# 4-RF-PD.net
KiCad netlist of a schematic drawn in Altium Designer
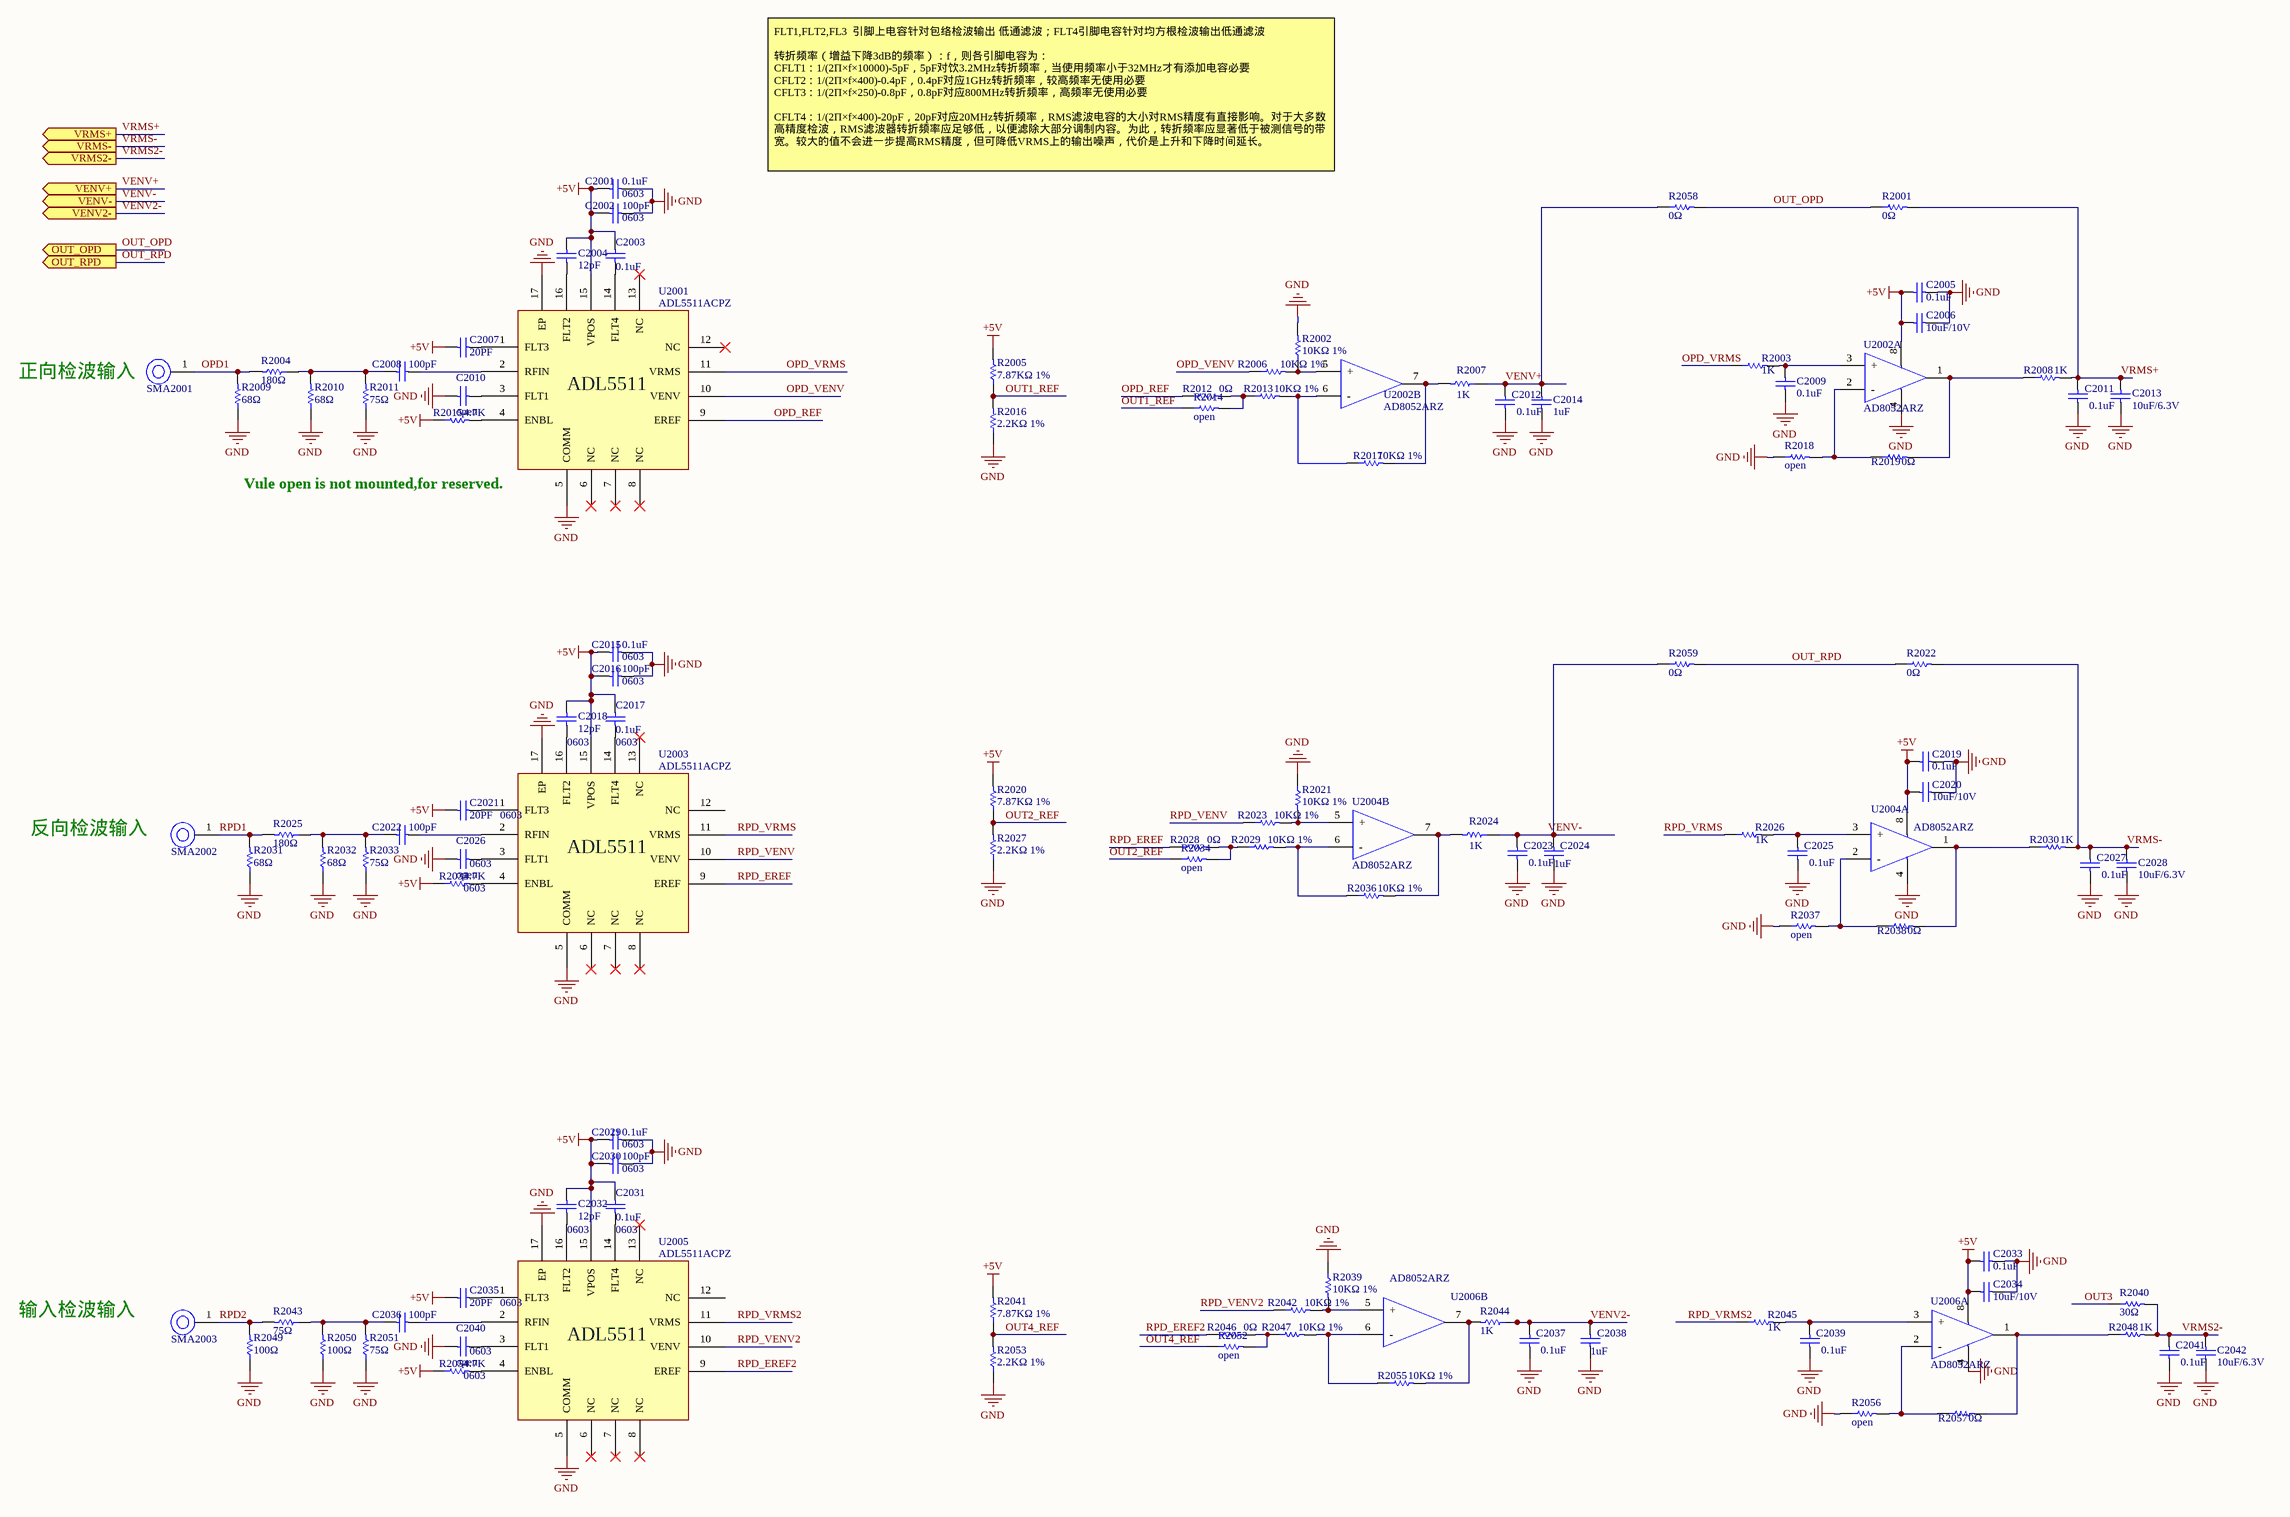
[diagram p0: 4-RF-PD.SchDoc]

(export (version "E")
  (design (tool "Eeschema 10.0.6"))
  (components
    (comp (ref "C2001")
      (value "0.1uF")
      (footprint "C0603")
      (description "贴片电容_GRM188R71H104KA01D_0.1uF±10%,50V,0603")
      (libsource (lib "20贴片电容0603") (part "0.1uF贴片电容"))
    )
    (comp (ref "C2002")
      (value "100pF")
      (footprint "C0603")
      (description "贴片电容_100pF±10%,50V,0603")
      (libsource (lib "20贴片电容0603") (part "1000pF贴片电容"))
    )
    (comp (ref "C2003")
      (value "0.1uF")
      (footprint "C0603")
      (description "贴片电容_GRM188R71H104KA01D_0.1uF±10%,50V,0603")
      (libsource (lib "20贴片电容0603") (part "0.1uF贴片电容"))
    )
    (comp (ref "C2004")
      (value "12pF")
      (footprint "C0603")
      (description "GRM1885C1H390JA01D_39pF±5%,50V,0603")
      (libsource (lib "20贴片电容0603") (part "10pF贴片电容"))
    )
    (comp (ref "C2005")
      (value "0.1uF")
      (footprint "C0603")
      (description "贴片电容_GRM188R71H104KA01D_0.1uF±10%,50V,0603")
      (libsource (lib "20贴片电容0603") (part "0.1uF贴片电容"))
    )
    (comp (ref "C2006")
      (value "10uF/10V")
      (footprint "C0805")
      (description "贴片电容_GRM21BR61A106KE19L_10uF±10%,10V,0805")
      (libsource (lib "21贴片电容0805") (part "10uF贴片电容"))
    )
    (comp (ref "C2007")
      (value "20PF")
      (footprint "C0603")
      (description "贴片电容_GRM1885C1H680JA01D_0603,68PF,50V,±5％,COG")
      (fields (field (name "MPN") "Murata"))
      (libsource (lib "20贴片电容0603") (part "10pF贴片电容"))
    )
    (comp (ref "C2008")
      (value "100pF")
      (footprint "C0805")
      (description "贴片电容_GRM2165C1H101JA01D_100pF±5%,50V,0805")
      (libsource (lib "21贴片电容0805") (part "100pF贴片电容"))
    )
    (comp (ref "C2009")
      (value "0.1uF")
      (footprint "C0603")
      (description "贴片电容_GRM188R71H104KA01D_0.1uF±10%,50V,0603")
      (libsource (lib "20贴片电容0603") (part "0.1uF贴片电容"))
    )
    (comp (ref "C2010")
      (value "open")
      (footprint "C0603")
      (description "贴片电容_GRM188R71H102KA01_1000pF±10%,50V,0603")
      (libsource (lib "20贴片电容0603") (part "1000pF贴片电容"))
    )
    (comp (ref "C2011")
      (value "0.1uF")
      (footprint "C0603")
      (description "贴片电容_GRM188R71H104KA01D_0.1uF±10%,50V,0603")
      (libsource (lib "20贴片电容0603") (part "0.1uF贴片电容"))
    )
    (comp (ref "C2012")
      (value "0.1uF")
      (footprint "C0603")
      (description "贴片电容_GRM188R71H104KA01D_0.1uF±10%,50V,0603")
      (libsource (lib "20贴片电容0603") (part "0.1uF贴片电容"))
    )
    (comp (ref "C2013")
      (value "10uF/6.3V")
      (footprint "C0603")
      (description "贴片电容_GRM188R60J106ME47D_10uF±20%,6.3V,0603")
      (libsource (lib "20贴片电容0603") (part "10uF贴片电容"))
    )
    (comp (ref "C2014") (value "1uF") (footprint "C0603") (libsource (lib "20贴片电容0603") (part "10uF贴片电容")))
    (comp (ref "C2015")
      (value "0.1uF")
      (footprint "C0603")
      (description "贴片电容_GRM188R71H104KA01D_0.1uF±10%,50V,0603")
      (libsource (lib "20贴片电容0603") (part "0.1uF贴片电容"))
    )
    (comp (ref "C2016")
      (value "100pF")
      (footprint "C0603")
      (description "贴片电容_100pF±10%,50V,0603")
      (libsource (lib "20贴片电容0603") (part "1000pF贴片电容"))
    )
    (comp (ref "C2017")
      (value "0.1uF")
      (footprint "C0603")
      (description "贴片电容_GRM188R71H104KA01D_0.1uF±10%,50V,0603")
      (libsource (lib "20贴片电容0603") (part "0.1uF贴片电容"))
    )
    (comp (ref "C2018")
      (value "12pF")
      (footprint "C0603")
      (description "GRM1885C1H390JA01D_39pF±5%,50V,0603")
      (libsource (lib "20贴片电容0603") (part "10pF贴片电容"))
    )
    (comp (ref "C2019")
      (value "0.1uF")
      (footprint "C0603")
      (description "贴片电容_GRM188R71H104KA01D_0.1uF±10%,50V,0603")
      (libsource (lib "20贴片电容0603") (part "0.1uF贴片电容"))
    )
    (comp (ref "C2020")
      (value "10uF/10V")
      (footprint "C0805")
      (description "贴片电容_GRM21BR61A106KE19L_10uF±10%,10V,0805")
      (libsource (lib "21贴片电容0805") (part "10uF贴片电容"))
    )
    (comp (ref "C2021")
      (value "20PF")
      (footprint "C0603")
      (description "贴片电容_GRM1885C1H680JA01D_0603,68PF,50V,±5％,COG")
      (fields (field (name "MPN") "Murata"))
      (libsource (lib "20贴片电容0603") (part "10pF贴片电容"))
    )
    (comp (ref "C2022")
      (value "100pF")
      (footprint "C0805")
      (description "贴片电容_GRM2165C1H101JA01D_100pF±5%,50V,0805")
      (libsource (lib "21贴片电容0805") (part "100pF贴片电容"))
    )
    (comp (ref "C2023")
      (value "0.1uF")
      (footprint "C0603")
      (description "贴片电容_GRM188R71H104KA01D_0.1uF±10%,50V,0603")
      (libsource (lib "20贴片电容0603") (part "0.1uF贴片电容"))
    )
    (comp (ref "C2024") (value "1uF") (footprint "C0603") (libsource (lib "20贴片电容0603") (part "10uF贴片电容")))
    (comp (ref "C2025")
      (value "0.1uF")
      (footprint "C0603")
      (description "贴片电容_GRM188R71H104KA01D_0.1uF±10%,50V,0603")
      (libsource (lib "20贴片电容0603") (part "0.1uF贴片电容"))
    )
    (comp (ref "C2026")
      (value "open")
      (footprint "C0603")
      (description "贴片电容_GRM188R71H102KA01_1000pF±10%,50V,0603")
      (libsource (lib "20贴片电容0603") (part "1000pF贴片电容"))
    )
    (comp (ref "C2027")
      (value "0.1uF")
      (footprint "C0603")
      (description "贴片电容_GRM188R71H104KA01D_0.1uF±10%,50V,0603")
      (libsource (lib "20贴片电容0603") (part "0.1uF贴片电容"))
    )
    (comp (ref "C2028")
      (value "10uF/6.3V")
      (footprint "C0603")
      (description "贴片电容_GRM188R60J106ME47D_10uF±20%,6.3V,0603")
      (libsource (lib "20贴片电容0603") (part "10uF贴片电容"))
    )
    (comp (ref "C2029")
      (value "0.1uF")
      (footprint "C0603")
      (description "贴片电容_GRM188R71H104KA01D_0.1uF±10%,50V,0603")
      (libsource (lib "20贴片电容0603") (part "0.1uF贴片电容"))
    )
    (comp (ref "C2030")
      (value "100pF")
      (footprint "C0603")
      (description "贴片电容_100pF±10%,50V,0603")
      (libsource (lib "20贴片电容0603") (part "1000pF贴片电容"))
    )
    (comp (ref "C2031")
      (value "0.1uF")
      (footprint "C0603")
      (description "贴片电容_GRM188R71H104KA01D_0.1uF±10%,50V,0603")
      (libsource (lib "20贴片电容0603") (part "0.1uF贴片电容"))
    )
    (comp (ref "C2032")
      (value "12pF")
      (footprint "C0603")
      (description "GRM1885C1H390JA01D_39pF±5%,50V,0603")
      (libsource (lib "20贴片电容0603") (part "10pF贴片电容"))
    )
    (comp (ref "C2033")
      (value "0.1uF")
      (footprint "C0603")
      (description "贴片电容_GRM188R71H104KA01D_0.1uF±10%,50V,0603")
      (libsource (lib "20贴片电容0603") (part "0.1uF贴片电容"))
    )
    (comp (ref "C2034")
      (value "10uF/10V")
      (footprint "C0805")
      (description "贴片电容_GRM21BR61A106KE19L_10uF±10%,10V,0805")
      (libsource (lib "21贴片电容0805") (part "10uF贴片电容"))
    )
    (comp (ref "C2035")
      (value "20PF")
      (footprint "C0603")
      (description "贴片电容_GRM1885C1H680JA01D_0603,68PF,50V,±5％,COG")
      (fields (field (name "MPN") "Murata"))
      (libsource (lib "20贴片电容0603") (part "10pF贴片电容"))
    )
    (comp (ref "C2036")
      (value "100pF")
      (footprint "C0805")
      (description "贴片电容_GRM2165C1H101JA01D_100pF±5%,50V,0805")
      (libsource (lib "21贴片电容0805") (part "100pF贴片电容"))
    )
    (comp (ref "C2037")
      (value "0.1uF")
      (footprint "C0603")
      (description "贴片电容_GRM188R71H104KA01D_0.1uF±10%,50V,0603")
      (libsource (lib "20贴片电容0603") (part "0.1uF贴片电容"))
    )
    (comp (ref "C2038") (value "1uF") (footprint "C0603") (libsource (lib "20贴片电容0603") (part "10uF贴片电容")))
    (comp (ref "C2039")
      (value "0.1uF")
      (footprint "C0603")
      (description "贴片电容_GRM188R71H104KA01D_0.1uF±10%,50V,0603")
      (libsource (lib "20贴片电容0603") (part "0.1uF贴片电容"))
    )
    (comp (ref "C2040")
      (value "open")
      (footprint "C0603")
      (description "贴片电容_GRM188R71H102KA01_1000pF±10%,50V,0603")
      (libsource (lib "20贴片电容0603") (part "1000pF贴片电容"))
    )
    (comp (ref "C2041")
      (value "0.1uF")
      (footprint "C0603")
      (description "贴片电容_GRM188R71H104KA01D_0.1uF±10%,50V,0603")
      (libsource (lib "20贴片电容0603") (part "0.1uF贴片电容"))
    )
    (comp (ref "C2042")
      (value "10uF/6.3V")
      (footprint "C0603")
      (description "贴片电容_GRM188R60J106ME47D_10uF±20%,6.3V,0603")
      (libsource (lib "20贴片电容0603") (part "10uF贴片电容"))
    )
    (comp (ref "R2001") (value "0Ω") (footprint "R0603") (libsource (lib "10贴片电阻0603") (part "0Ω贴片电阻")))
    (comp (ref "R2002")
      (value "10KΩ 1%")
      (footprint "R0603")
      (libsource (lib "10贴片电阻0603") (part "430Ω贴片电阻"))
    )
    (comp (ref "R2003")
      (value "1K")
      (footprint "R0603")
      (description "贴片电阻_1K±5%,0603")
      (libsource (lib "10贴片电阻0603") (part "1K贴片电阻"))
    )
    (comp (ref "R2004")
      (value "180Ω")
      (footprint "R1206")
      (description "贴片电阻_1206,180Ω,±5％")
      (libsource (lib "12贴片电阻1206") (part "56Ω贴片电阻"))
    )
    (comp (ref "R2005")
      (value "7.87KΩ 1%")
      (footprint "R0603")
      (description "0603,7.87KΩ,±1％")
      (libsource (lib "10贴片电阻0603") (part "0Ω贴片电阻"))
    )
    (comp (ref "R2006")
      (value "10KΩ 1%")
      (footprint "R0603")
      (libsource (lib "10贴片电阻0603") (part "430Ω贴片电阻"))
    )
    (comp (ref "R2007") (value "1K") (footprint "R0603") (libsource (lib "10贴片电阻0603") (part "0Ω贴片电阻")))
    (comp (ref "R2008")
      (value "1K")
      (footprint "R0603")
      (description "贴片电阻_0Ω±5%,0603")
      (libsource (lib "10贴片电阻0603") (part "0Ω贴片电阻"))
    )
    (comp (ref "R2009")
      (value "68Ω")
      (footprint "R1206")
      (description "贴片电阻_68Ω±5%,1206")
      (libsource (lib "12贴片电阻1206") (part "56Ω贴片电阻"))
    )
    (comp (ref "R2010")
      (value "68Ω")
      (footprint "R1206")
      (description "贴片电阻_68Ω±5%,1206")
      (libsource (lib "12贴片电阻1206") (part "56Ω贴片电阻"))
    )
    (comp (ref "R2011")
      (value "75Ω")
      (footprint "R0805")
      (description "贴片电阻_75Ω±5%,0805")
      (libsource (lib "11贴片电阻0805") (part "75Ω贴片电阻"))
    )
    (comp (ref "R2012")
      (value "0Ω")
      (footprint "R0603")
      (description "贴片电阻_0Ω±5%,0603")
      (libsource (lib "10贴片电阻0603") (part "0Ω贴片电阻"))
    )
    (comp (ref "R2013")
      (value "10KΩ 1%")
      (footprint "R0603")
      (libsource (lib "10贴片电阻0603") (part "430Ω贴片电阻"))
    )
    (comp (ref "R2014")
      (value "open")
      (footprint "R0603")
      (description "贴片电阻_0Ω±5%,0603")
      (libsource (lib "10贴片电阻0603") (part "0Ω贴片电阻"))
    )
    (comp (ref "R2015")
      (value "4.7K")
      (footprint "R0603")
      (description "贴片电阻_4.7K±5%,0603")
      (libsource (lib "10贴片电阻0603") (part "4.7K贴片电阻"))
    )
    (comp (ref "R2016")
      (value "2.2KΩ 1%")
      (footprint "R0603")
      (description "0603,2.2KΩ,±1％")
      (libsource (lib "10贴片电阻0603") (part "0Ω贴片电阻"))
    )
    (comp (ref "R2017")
      (value "10KΩ 1%")
      (footprint "R0603")
      (libsource (lib "10贴片电阻0603") (part "430Ω贴片电阻"))
    )
    (comp (ref "R2018") (value "open") (footprint "R0603") (libsource (lib "10贴片电阻0603") (part "0Ω贴片电阻")))
    (comp (ref "R2019")
      (value "0Ω")
      (footprint "R0603")
      (description "贴片电阻_0Ω±5%,0603")
      (libsource (lib "10贴片电阻0603") (part "0Ω贴片电阻"))
    )
    (comp (ref "R2020")
      (value "7.87KΩ 1%")
      (footprint "R0603")
      (description "0603,7.87KΩ,±1％")
      (libsource (lib "10贴片电阻0603") (part "0Ω贴片电阻"))
    )
    (comp (ref "R2021")
      (value "10KΩ 1%")
      (footprint "R0603")
      (libsource (lib "10贴片电阻0603") (part "430Ω贴片电阻"))
    )
    (comp (ref "R2022") (value "0Ω") (footprint "R0603") (libsource (lib "10贴片电阻0603") (part "0Ω贴片电阻")))
    (comp (ref "R2023")
      (value "10KΩ 1%")
      (footprint "R0603")
      (libsource (lib "10贴片电阻0603") (part "430Ω贴片电阻"))
    )
    (comp (ref "R2024") (value "1K") (footprint "R0603") (libsource (lib "10贴片电阻0603") (part "0Ω贴片电阻")))
    (comp (ref "R2025")
      (value "180Ω")
      (footprint "R1206")
      (description "贴片电阻_1206,180Ω,±5％")
      (libsource (lib "12贴片电阻1206") (part "56Ω贴片电阻"))
    )
    (comp (ref "R2026")
      (value "1K")
      (footprint "R0603")
      (description "贴片电阻_1K±5%,0603")
      (libsource (lib "10贴片电阻0603") (part "1K贴片电阻"))
    )
    (comp (ref "R2027")
      (value "2.2KΩ 1%")
      (footprint "R0603")
      (description "0603,2.2KΩ,±1％")
      (libsource (lib "10贴片电阻0603") (part "0Ω贴片电阻"))
    )
    (comp (ref "R2028")
      (value "0Ω")
      (footprint "R0603")
      (description "贴片电阻_0Ω±5%,0603")
      (libsource (lib "10贴片电阻0603") (part "0Ω贴片电阻"))
    )
    (comp (ref "R2029")
      (value "10KΩ 1%")
      (footprint "R0603")
      (libsource (lib "10贴片电阻0603") (part "430Ω贴片电阻"))
    )
    (comp (ref "R2030")
      (value "1K")
      (footprint "R0603")
      (description "贴片电阻_0Ω±5%,0603")
      (libsource (lib "10贴片电阻0603") (part "0Ω贴片电阻"))
    )
    (comp (ref "R2031")
      (value "68Ω")
      (footprint "R1206")
      (description "贴片电阻_68Ω±5%,1206")
      (libsource (lib "12贴片电阻1206") (part "56Ω贴片电阻"))
    )
    (comp (ref "R2032")
      (value "68Ω")
      (footprint "R1206")
      (description "贴片电阻_68Ω±5%,1206")
      (libsource (lib "12贴片电阻1206") (part "56Ω贴片电阻"))
    )
    (comp (ref "R2033")
      (value "75Ω")
      (footprint "R0805")
      (description "贴片电阻_75Ω±5%,0805")
      (libsource (lib "11贴片电阻0805") (part "75Ω贴片电阻"))
    )
    (comp (ref "R2034")
      (value "open")
      (footprint "R0603")
      (description "贴片电阻_0Ω±5%,0603")
      (libsource (lib "10贴片电阻0603") (part "0Ω贴片电阻"))
    )
    (comp (ref "R2035")
      (value "4.7K")
      (footprint "R0603")
      (description "贴片电阻_4.7K±5%,0603")
      (libsource (lib "10贴片电阻0603") (part "4.7K贴片电阻"))
    )
    (comp (ref "R2036")
      (value "10KΩ 1%")
      (footprint "R0603")
      (libsource (lib "10贴片电阻0603") (part "430Ω贴片电阻"))
    )
    (comp (ref "R2037") (value "open") (footprint "R0603") (libsource (lib "10贴片电阻0603") (part "0Ω贴片电阻")))
    (comp (ref "R2038")
      (value "0Ω")
      (footprint "R0603")
      (description "贴片电阻_0Ω±5%,0603")
      (libsource (lib "10贴片电阻0603") (part "0Ω贴片电阻"))
    )
    (comp (ref "R2039")
      (value "10KΩ 1%")
      (footprint "R0603")
      (libsource (lib "10贴片电阻0603") (part "430Ω贴片电阻"))
    )
    (comp (ref "R2040") (value "30Ω") (footprint "R0603") (libsource (lib "10贴片电阻0603") (part "0Ω贴片电阻")))
    (comp (ref "R2041")
      (value "7.87KΩ 1%")
      (footprint "R0603")
      (description "0603,7.87KΩ,±1％")
      (libsource (lib "10贴片电阻0603") (part "0Ω贴片电阻"))
    )
    (comp (ref "R2042")
      (value "10KΩ 1%")
      (footprint "R0603")
      (libsource (lib "10贴片电阻0603") (part "430Ω贴片电阻"))
    )
    (comp (ref "R2043")
      (value "75Ω")
      (footprint "R1206")
      (description "贴片电阻_75Ω±5%,1206")
      (libsource (lib "12贴片电阻1206") (part "56Ω贴片电阻"))
    )
    (comp (ref "R2044") (value "1K") (footprint "R0603") (libsource (lib "10贴片电阻0603") (part "0Ω贴片电阻")))
    (comp (ref "R2045")
      (value "1K")
      (footprint "R0603")
      (description "贴片电阻_1K±5%,0603")
      (libsource (lib "10贴片电阻0603") (part "1K贴片电阻"))
    )
    (comp (ref "R2046")
      (value "0Ω")
      (footprint "R0603")
      (description "贴片电阻_0Ω±5%,0603")
      (libsource (lib "10贴片电阻0603") (part "0Ω贴片电阻"))
    )
    (comp (ref "R2047")
      (value "10KΩ 1%")
      (footprint "R0603")
      (libsource (lib "10贴片电阻0603") (part "430Ω贴片电阻"))
    )
    (comp (ref "R2048")
      (value "1K")
      (footprint "R0603")
      (description "贴片电阻_0Ω±5%,0603")
      (libsource (lib "10贴片电阻0603") (part "0Ω贴片电阻"))
    )
    (comp (ref "R2049")
      (value "100Ω")
      (footprint "R1206")
      (description "贴片电阻_100Ω±5%,1206")
      (libsource (lib "12贴片电阻1206") (part "56Ω贴片电阻"))
    )
    (comp (ref "R2050")
      (value "100Ω")
      (footprint "R1206")
      (description "贴片电阻_100Ω±5%,1206")
      (libsource (lib "12贴片电阻1206") (part "56Ω贴片电阻"))
    )
    (comp (ref "R2051")
      (value "75Ω")
      (footprint "R0805")
      (description "贴片电阻_75Ω±5%,0805")
      (libsource (lib "11贴片电阻0805") (part "75Ω贴片电阻"))
    )
    (comp (ref "R2052")
      (value "open")
      (footprint "R0603")
      (description "贴片电阻_0Ω±5%,0603")
      (libsource (lib "10贴片电阻0603") (part "0Ω贴片电阻"))
    )
    (comp (ref "R2053")
      (value "2.2KΩ 1%")
      (footprint "R0603")
      (description "0603,2.2KΩ,±1％")
      (libsource (lib "10贴片电阻0603") (part "0Ω贴片电阻"))
    )
    (comp (ref "R2054")
      (value "4.7K")
      (footprint "R0603")
      (description "贴片电阻_4.7K±5%,0603")
      (libsource (lib "10贴片电阻0603") (part "4.7K贴片电阻"))
    )
    (comp (ref "R2055")
      (value "10KΩ 1%")
      (footprint "R0603")
      (libsource (lib "10贴片电阻0603") (part "430Ω贴片电阻"))
    )
    (comp (ref "R2056") (value "open") (footprint "R0603") (libsource (lib "10贴片电阻0603") (part "0Ω贴片电阻")))
    (comp (ref "R2057")
      (value "0Ω")
      (footprint "R0603")
      (description "贴片电阻_0Ω±5%,0603")
      (libsource (lib "10贴片电阻0603") (part "0Ω贴片电阻"))
    )
    (comp (ref "R2058") (value "0Ω") (footprint "R0603") (libsource (lib "10贴片电阻0603") (part "0Ω贴片电阻")))
    (comp (ref "R2059") (value "0Ω") (footprint "R0603") (libsource (lib "10贴片电阻0603") (part "0Ω贴片电阻")))
    (comp (ref "SMA2001")
      (value "SMA-50KFD-4")
      (footprint "SMA-50KFD-4")
      (description "射频同轴连接器_SMA-50KFD-4")
      (libsource (lib "90RF连接器") (part "SMA-50KFD-4"))
    )
    (comp (ref "SMA2002")
      (value "SMA-50KFD-4")
      (footprint "SMA-50KFD-4")
      (description "射频同轴连接器_SMA-50KFD-4")
      (libsource (lib "90RF连接器") (part "SMA-50KFD-4"))
    )
    (comp (ref "SMA2003")
      (value "SMA-50KFD-4")
      (footprint "SMA-50KFD-4")
      (description "射频同轴连接器_SMA-50KFD-4")
      (libsource (lib "90RF连接器") (part "SMA-50KFD-4"))
    )
    (comp (ref "U2001")
      (value "ADL5511ACPZ")
      (footprint "QFN16_0R50_3X3")
      (description "检波器_ADL5511ACPZ_DC~6GHz,LFCSP16")
      (libsource (lib "74检波器") (part "ADL5511ACPZ"))
    )
    (comp (ref "U2002")
      (value "AD8052ARZ")
      (footprint "SOIC8_1R27_3R9x4R9")
      (libsource (lib "77运算放大器") (part "OP284"))
    )
    (comp (ref "U2003")
      (value "ADL5511ACPZ")
      (footprint "QFN16_0R50_3X3")
      (description "检波器_ADL5511ACPZ_DC~6GHz,LFCSP16")
      (libsource (lib "74检波器") (part "ADL5511ACPZ"))
    )
    (comp (ref "U2004")
      (value "AD8052ARZ")
      (footprint "SOIC8_1R27_3R9x4R9")
      (description "运算放大器_LM358_SOIC8")
      (libsource (lib "77运算放大器") (part "LM358"))
    )
    (comp (ref "U2005")
      (value "ADL5511ACPZ")
      (footprint "QFN16_0R50_3X3")
      (description "检波器_ADL5511ACPZ_DC~6GHz,LFCSP16")
      (libsource (lib "74检波器") (part "ADL5511ACPZ"))
    )
    (comp (ref "U2006")
      (value "AD8052ARZ")
      (footprint "SOIC8_1R27_3R9x4R9")
      (libsource (lib "77运算放大器") (part "OP284"))
    )
  )
  (nets
    (net (code "1") (name "+5V") (class "Default")
      (node (ref "C2001") (pin "2") (pinfunction "2_2") (pintype "passive"))
      (node (ref "C2002") (pin "1") (pinfunction "1_1") (pintype "passive"))
      (node (ref "C2003") (pin "2") (pinfunction "2_2") (pintype "passive"))
      (node (ref "C2004") (pin "2") (pinfunction "2_2") (pintype "passive"))
      (node (ref "C2005") (pin "1") (pinfunction "1_1") (pintype "passive"))
      (node (ref "C2006") (pin "1") (pinfunction "1_1") (pintype "passive"))
      (node (ref "C2007") (pin "1") (pinfunction "1_1") (pintype "passive"))
      (node (ref "C2015") (pin "2") (pinfunction "2_2") (pintype "passive"))
      (node (ref "C2016") (pin "1") (pinfunction "1_1") (pintype "passive"))
      (node (ref "C2017") (pin "2") (pinfunction "2_2") (pintype "passive"))
      (node (ref "C2018") (pin "2") (pinfunction "2_2") (pintype "passive"))
      (node (ref "C2019") (pin "1") (pinfunction "1_1") (pintype "passive"))
      (node (ref "C2020") (pin "1") (pinfunction "1_1") (pintype "passive"))
      (node (ref "C2021") (pin "1") (pinfunction "1_1") (pintype "passive"))
      (node (ref "C2029") (pin "2") (pinfunction "2_2") (pintype "passive"))
      (node (ref "C2030") (pin "1") (pinfunction "1_1") (pintype "passive"))
      (node (ref "C2031") (pin "2") (pinfunction "2_2") (pintype "passive"))
      (node (ref "C2032") (pin "2") (pinfunction "2_2") (pintype "passive"))
      (node (ref "C2033") (pin "1") (pinfunction "1_1") (pintype "passive"))
      (node (ref "C2034") (pin "1") (pinfunction "1_1") (pintype "passive"))
      (node (ref "C2035") (pin "1") (pinfunction "1_1") (pintype "passive"))
      (node (ref "R2005") (pin "2") (pinfunction "2_2") (pintype "passive"))
      (node (ref "R2015") (pin "1") (pinfunction "1_1") (pintype "passive"))
      (node (ref "R2020") (pin "2") (pinfunction "2_2") (pintype "passive"))
      (node (ref "R2035") (pin "1") (pinfunction "1_1") (pintype "passive"))
      (node (ref "R2041") (pin "2") (pinfunction "2_2") (pintype "passive"))
      (node (ref "R2054") (pin "1") (pinfunction "1_1") (pintype "passive"))
      (node (ref "U2001") (pin "15") (pinfunction "VPOS_15") (pintype "passive"))
      (node (ref "U2002") (pin "8") (pintype "passive"))
      (node (ref "U2003") (pin "15") (pinfunction "VPOS_15") (pintype "passive"))
      (node (ref "U2004") (pin "8") (pintype "passive"))
      (node (ref "U2005") (pin "15") (pinfunction "VPOS_15") (pintype "passive"))
      (node (ref "U2006") (pin "8") (pintype "passive"))
    )
    (net (code "2") (name "/OPD1") (class "Default")
      (node (ref "R2004") (pin "2") (pinfunction "2_2") (pintype "passive"))
      (node (ref "R2009") (pin "2") (pinfunction "2_2") (pintype "passive"))
      (node (ref "SMA2001") (pin "1") (pinfunction "Sig_1") (pintype "passive"))
    )
    (net (code "3") (name "/OPD_REF") (class "Default")
      (node (ref "R2012") (pin "1") (pinfunction "1_1") (pintype "passive"))
      (node (ref "U2001") (pin "9") (pinfunction "EREF_9") (pintype "passive"))
    )
    (net (code "4") (name "/OPD_VENV") (class "Default")
      (node (ref "R2006") (pin "1") (pinfunction "1_1") (pintype "passive"))
      (node (ref "U2001") (pin "10") (pinfunction "VENV_10") (pintype "passive"))
    )
    (net (code "5") (name "/OPD_VRMS") (class "Default")
      (node (ref "R2003") (pin "1") (pinfunction "1_1") (pintype "passive"))
      (node (ref "U2001") (pin "11") (pinfunction "VRMS_11") (pintype "passive"))
    )
    (net (code "6") (name "/OUT1_REF") (class "Default")
      (node (ref "R2005") (pin "1") (pinfunction "1_1") (pintype "passive"))
      (node (ref "R2014") (pin "1") (pinfunction "1_1") (pintype "passive"))
      (node (ref "R2016") (pin "2") (pinfunction "2_2") (pintype "passive"))
    )
    (net (code "7") (name "/OUT2_REF") (class "Default")
      (node (ref "R2020") (pin "1") (pinfunction "1_1") (pintype "passive"))
      (node (ref "R2027") (pin "2") (pinfunction "2_2") (pintype "passive"))
      (node (ref "R2034") (pin "1") (pinfunction "1_1") (pintype "passive"))
    )
    (net (code "8") (name "/OUT3") (class "Default")
      (node (ref "R2040") (pin "1") (pinfunction "1_1") (pintype "passive"))
    )
    (net (code "9") (name "/OUT4_REF") (class "Default")
      (node (ref "R2041") (pin "1") (pinfunction "1_1") (pintype "passive"))
      (node (ref "R2052") (pin "1") (pinfunction "1_1") (pintype "passive"))
      (node (ref "R2053") (pin "2") (pinfunction "2_2") (pintype "passive"))
    )
    (net (code "10") (name "/OUT_OPD") (class "Default")
      (node (ref "R2001") (pin "1") (pinfunction "1_1") (pintype "passive"))
      (node (ref "R2058") (pin "2") (pinfunction "2_2") (pintype "passive"))
    )
    (net (code "11") (name "/OUT_RPD") (class "Default")
      (node (ref "R2022") (pin "1") (pinfunction "1_1") (pintype "passive"))
      (node (ref "R2059") (pin "2") (pinfunction "2_2") (pintype "passive"))
    )
    (net (code "12") (name "/RPD1") (class "Default")
      (node (ref "R2025") (pin "2") (pinfunction "2_2") (pintype "passive"))
      (node (ref "R2031") (pin "2") (pinfunction "2_2") (pintype "passive"))
      (node (ref "SMA2002") (pin "1") (pinfunction "Sig_1") (pintype "passive"))
    )
    (net (code "13") (name "/RPD2") (class "Default")
      (node (ref "R2043") (pin "2") (pinfunction "2_2") (pintype "passive"))
      (node (ref "R2049") (pin "2") (pinfunction "2_2") (pintype "passive"))
      (node (ref "SMA2003") (pin "1") (pinfunction "Sig_1") (pintype "passive"))
    )
    (net (code "14") (name "/RPD_EREF") (class "Default")
      (node (ref "R2028") (pin "1") (pinfunction "1_1") (pintype "passive"))
      (node (ref "U2003") (pin "9") (pinfunction "EREF_9") (pintype "passive"))
    )
    (net (code "15") (name "/RPD_EREF2") (class "Default")
      (node (ref "R2046") (pin "1") (pinfunction "1_1") (pintype "passive"))
      (node (ref "U2005") (pin "9") (pinfunction "EREF_9") (pintype "passive"))
    )
    (net (code "16") (name "/RPD_VENV") (class "Default")
      (node (ref "R2023") (pin "1") (pinfunction "1_1") (pintype "passive"))
      (node (ref "U2003") (pin "10") (pinfunction "VENV_10") (pintype "passive"))
    )
    (net (code "17") (name "/RPD_VENV2") (class "Default")
      (node (ref "R2042") (pin "1") (pinfunction "1_1") (pintype "passive"))
      (node (ref "U2005") (pin "10") (pinfunction "VENV_10") (pintype "passive"))
    )
    (net (code "18") (name "/RPD_VRMS") (class "Default")
      (node (ref "R2026") (pin "1") (pinfunction "1_1") (pintype "passive"))
      (node (ref "U2003") (pin "11") (pinfunction "VRMS_11") (pintype "passive"))
    )
    (net (code "19") (name "/RPD_VRMS2") (class "Default")
      (node (ref "R2045") (pin "1") (pinfunction "1_1") (pintype "passive"))
      (node (ref "U2005") (pin "11") (pinfunction "VRMS_11") (pintype "passive"))
    )
    (net (code "20") (name "/VENV+") (class "Default")
      (node (ref "C2012") (pin "2") (pinfunction "2_2") (pintype "passive"))
      (node (ref "C2014") (pin "2") (pinfunction "2_2") (pintype "passive"))
      (node (ref "R2007") (pin "1") (pinfunction "1_1") (pintype "passive"))
      (node (ref "R2058") (pin "1") (pinfunction "1_1") (pintype "passive"))
    )
    (net (code "21") (name "/VENV-") (class "Default")
      (node (ref "C2023") (pin "2") (pinfunction "2_2") (pintype "passive"))
      (node (ref "C2024") (pin "2") (pinfunction "2_2") (pintype "passive"))
      (node (ref "R2024") (pin "1") (pinfunction "1_1") (pintype "passive"))
      (node (ref "R2059") (pin "1") (pinfunction "1_1") (pintype "passive"))
    )
    (net (code "22") (name "/VENV2-") (class "Default")
      (node (ref "C2037") (pin "2") (pinfunction "2_2") (pintype "passive"))
      (node (ref "C2038") (pin "2") (pinfunction "2_2") (pintype "passive"))
      (node (ref "R2044") (pin "1") (pinfunction "1_1") (pintype "passive"))
    )
    (net (code "23") (name "/VRMS+") (class "Default")
      (node (ref "C2011") (pin "2") (pinfunction "2_2") (pintype "passive"))
      (node (ref "C2013") (pin "2") (pinfunction "2_2") (pintype "passive"))
      (node (ref "R2001") (pin "2") (pinfunction "2_2") (pintype "passive"))
      (node (ref "R2008") (pin "2") (pinfunction "2_2") (pintype "passive"))
    )
    (net (code "24") (name "/VRMS-") (class "Default")
      (node (ref "C2027") (pin "2") (pinfunction "2_2") (pintype "passive"))
      (node (ref "C2028") (pin "2") (pinfunction "2_2") (pintype "passive"))
      (node (ref "R2022") (pin "2") (pinfunction "2_2") (pintype "passive"))
      (node (ref "R2030") (pin "2") (pinfunction "2_2") (pintype "passive"))
    )
    (net (code "25") (name "/VRMS2-") (class "Default")
      (node (ref "C2041") (pin "2") (pinfunction "2_2") (pintype "passive"))
      (node (ref "C2042") (pin "2") (pinfunction "2_2") (pintype "passive"))
      (node (ref "R2040") (pin "2") (pinfunction "2_2") (pintype "passive"))
      (node (ref "R2048") (pin "2") (pinfunction "2_2") (pintype "passive"))
    )
    (net (code "26") (name "GND") (class "Default")
      (node (ref "C2001") (pin "1") (pinfunction "1_1") (pintype "passive"))
      (node (ref "C2002") (pin "2") (pinfunction "2_2") (pintype "passive"))
      (node (ref "C2005") (pin "2") (pinfunction "2_2") (pintype "passive"))
      (node (ref "C2006") (pin "2") (pinfunction "2_2") (pintype "passive"))
      (node (ref "C2009") (pin "1") (pinfunction "1_1") (pintype "passive"))
      (node (ref "C2010") (pin "1") (pinfunction "1_1") (pintype "passive"))
      (node (ref "C2011") (pin "1") (pinfunction "1_1") (pintype "passive"))
      (node (ref "C2012") (pin "1") (pinfunction "1_1") (pintype "passive"))
      (node (ref "C2013") (pin "1") (pinfunction "1_1") (pintype "passive"))
      (node (ref "C2014") (pin "1") (pinfunction "1_1") (pintype "passive"))
      (node (ref "C2015") (pin "1") (pinfunction "1_1") (pintype "passive"))
      (node (ref "C2016") (pin "2") (pinfunction "2_2") (pintype "passive"))
      (node (ref "C2019") (pin "2") (pinfunction "2_2") (pintype "passive"))
      (node (ref "C2020") (pin "2") (pinfunction "2_2") (pintype "passive"))
      (node (ref "C2023") (pin "1") (pinfunction "1_1") (pintype "passive"))
      (node (ref "C2024") (pin "1") (pinfunction "1_1") (pintype "passive"))
      (node (ref "C2025") (pin "1") (pinfunction "1_1") (pintype "passive"))
      (node (ref "C2026") (pin "1") (pinfunction "1_1") (pintype "passive"))
      (node (ref "C2027") (pin "1") (pinfunction "1_1") (pintype "passive"))
      (node (ref "C2028") (pin "1") (pinfunction "1_1") (pintype "passive"))
      (node (ref "C2029") (pin "1") (pinfunction "1_1") (pintype "passive"))
      (node (ref "C2030") (pin "2") (pinfunction "2_2") (pintype "passive"))
      (node (ref "C2033") (pin "2") (pinfunction "2_2") (pintype "passive"))
      (node (ref "C2034") (pin "2") (pinfunction "2_2") (pintype "passive"))
      (node (ref "C2037") (pin "1") (pinfunction "1_1") (pintype "passive"))
      (node (ref "C2038") (pin "1") (pinfunction "1_1") (pintype "passive"))
      (node (ref "C2039") (pin "1") (pinfunction "1_1") (pintype "passive"))
      (node (ref "C2040") (pin "1") (pinfunction "1_1") (pintype "passive"))
      (node (ref "C2041") (pin "1") (pinfunction "1_1") (pintype "passive"))
      (node (ref "C2042") (pin "1") (pinfunction "1_1") (pintype "passive"))
      (node (ref "R2002") (pin "2") (pinfunction "2_2") (pintype "passive"))
      (node (ref "R2009") (pin "1") (pinfunction "1_1") (pintype "passive"))
      (node (ref "R2010") (pin "1") (pinfunction "1_1") (pintype "passive"))
      (node (ref "R2011") (pin "1") (pinfunction "1_1") (pintype "passive"))
      (node (ref "R2016") (pin "1") (pinfunction "1_1") (pintype "passive"))
      (node (ref "R2018") (pin "1") (pinfunction "1_1") (pintype "passive"))
      (node (ref "R2021") (pin "1") (pinfunction "1_1") (pintype "passive"))
      (node (ref "R2027") (pin "1") (pinfunction "1_1") (pintype "passive"))
      (node (ref "R2031") (pin "1") (pinfunction "1_1") (pintype "passive"))
      (node (ref "R2032") (pin "1") (pinfunction "1_1") (pintype "passive"))
      (node (ref "R2033") (pin "1") (pinfunction "1_1") (pintype "passive"))
      (node (ref "R2037") (pin "1") (pinfunction "1_1") (pintype "passive"))
      (node (ref "R2039") (pin "1") (pinfunction "1_1") (pintype "passive"))
      (node (ref "R2049") (pin "1") (pinfunction "1_1") (pintype "passive"))
      (node (ref "R2050") (pin "1") (pinfunction "1_1") (pintype "passive"))
      (node (ref "R2051") (pin "1") (pinfunction "1_1") (pintype "passive"))
      (node (ref "R2053") (pin "1") (pinfunction "1_1") (pintype "passive"))
      (node (ref "R2056") (pin "1") (pinfunction "1_1") (pintype "passive"))
      (node (ref "U2001") (pin "17") (pinfunction "EP_17") (pintype "power_in"))
      (node (ref "U2001") (pin "5") (pinfunction "COMM_5") (pintype "passive"))
      (node (ref "U2002") (pin "4") (pintype "passive"))
      (node (ref "U2003") (pin "17") (pinfunction "EP_17") (pintype "power_in"))
      (node (ref "U2003") (pin "5") (pinfunction "COMM_5") (pintype "passive"))
      (node (ref "U2004") (pin "4") (pintype "passive"))
      (node (ref "U2005") (pin "17") (pinfunction "EP_17") (pintype "power_in"))
      (node (ref "U2005") (pin "5") (pinfunction "COMM_5") (pintype "passive"))
      (node (ref "U2006") (pin "4") (pintype "passive"))
    )
    (net (code "27") (name "Net-(C2008-Pad1)") (class "Default")
      (node (ref "C2008") (pin "1") (pinfunction "1_1") (pintype "passive"))
      (node (ref "R2004") (pin "1") (pinfunction "1_1") (pintype "passive"))
      (node (ref "R2010") (pin "2") (pinfunction "2_2") (pintype "passive"))
      (node (ref "R2011") (pin "2") (pinfunction "2_2") (pintype "passive"))
    )
    (net (code "28") (name "Net-(C2022-Pad1)") (class "Default")
      (node (ref "C2022") (pin "1") (pinfunction "1_1") (pintype "passive"))
      (node (ref "R2025") (pin "1") (pinfunction "1_1") (pintype "passive"))
      (node (ref "R2032") (pin "2") (pinfunction "2_2") (pintype "passive"))
      (node (ref "R2033") (pin "2") (pinfunction "2_2") (pintype "passive"))
    )
    (net (code "29") (name "Net-(C2036-Pad1)") (class "Default")
      (node (ref "C2036") (pin "1") (pinfunction "1_1") (pintype "passive"))
      (node (ref "R2043") (pin "1") (pinfunction "1_1") (pintype "passive"))
      (node (ref "R2050") (pin "2") (pinfunction "2_2") (pintype "passive"))
      (node (ref "R2051") (pin "2") (pinfunction "2_2") (pintype "passive"))
    )
    (net (code "30") (name "Net-(R2007-Pad2)") (class "Default")
      (node (ref "R2007") (pin "2") (pinfunction "2_2") (pintype "passive"))
      (node (ref "R2017") (pin "2") (pinfunction "2_2") (pintype "passive"))
      (node (ref "U2002") (pin "7") (pintype "passive"))
    )
    (net (code "31") (name "Net-(R2008-Pad1)") (class "Default")
      (node (ref "R2008") (pin "1") (pinfunction "1_1") (pintype "passive"))
      (node (ref "R2019") (pin "2") (pinfunction "2_2") (pintype "passive"))
      (node (ref "U2002") (pin "1") (pintype "passive"))
    )
    (net (code "32") (name "Net-(R2012-Pad2)") (class "Default")
      (node (ref "R2012") (pin "2") (pinfunction "2_2") (pintype "passive"))
      (node (ref "R2013") (pin "1") (pinfunction "1_1") (pintype "passive"))
      (node (ref "R2014") (pin "2") (pinfunction "2_2") (pintype "passive"))
    )
    (net (code "33") (name "Net-(R2024-Pad2)") (class "Default")
      (node (ref "R2024") (pin "2") (pinfunction "2_2") (pintype "passive"))
      (node (ref "R2036") (pin "2") (pinfunction "2_2") (pintype "passive"))
      (node (ref "U2004") (pin "7") (pintype "passive"))
    )
    (net (code "34") (name "Net-(R2028-Pad2)") (class "Default")
      (node (ref "R2028") (pin "2") (pinfunction "2_2") (pintype "passive"))
      (node (ref "R2029") (pin "1") (pinfunction "1_1") (pintype "passive"))
      (node (ref "R2034") (pin "2") (pinfunction "2_2") (pintype "passive"))
    )
    (net (code "35") (name "Net-(R2030-Pad1)") (class "Default")
      (node (ref "R2030") (pin "1") (pinfunction "1_1") (pintype "passive"))
      (node (ref "R2038") (pin "2") (pinfunction "2_2") (pintype "passive"))
      (node (ref "U2004") (pin "1") (pintype "passive"))
    )
    (net (code "36") (name "Net-(R2044-Pad2)") (class "Default")
      (node (ref "R2044") (pin "2") (pinfunction "2_2") (pintype "passive"))
      (node (ref "R2055") (pin "2") (pinfunction "2_2") (pintype "passive"))
      (node (ref "U2006") (pin "7") (pintype "passive"))
    )
    (net (code "37") (name "Net-(R2046-Pad2)") (class "Default")
      (node (ref "R2046") (pin "2") (pinfunction "2_2") (pintype "passive"))
      (node (ref "R2047") (pin "1") (pinfunction "1_1") (pintype "passive"))
      (node (ref "R2052") (pin "2") (pinfunction "2_2") (pintype "passive"))
    )
    (net (code "38") (name "Net-(R2048-Pad1)") (class "Default")
      (node (ref "R2048") (pin "1") (pinfunction "1_1") (pintype "passive"))
      (node (ref "R2057") (pin "2") (pinfunction "2_2") (pintype "passive"))
      (node (ref "U2006") (pin "1") (pintype "passive"))
    )
    (net (code "39") (name "Net-(U2001-ENBL)") (class "Default")
      (node (ref "R2015") (pin "2") (pinfunction "2_2") (pintype "passive"))
      (node (ref "U2001") (pin "4") (pinfunction "ENBL_4") (pintype "passive"))
    )
    (net (code "40") (name "Net-(U2001-FLT1)") (class "Default")
      (node (ref "C2010") (pin "2") (pinfunction "2_2") (pintype "passive"))
      (node (ref "U2001") (pin "3") (pinfunction "FLT1_3") (pintype "passive"))
    )
    (net (code "41") (name "Net-(U2001-FLT2)") (class "Default")
      (node (ref "C2004") (pin "1") (pinfunction "1_1") (pintype "passive"))
      (node (ref "U2001") (pin "16") (pinfunction "FLT2_16") (pintype "passive"))
    )
    (net (code "42") (name "Net-(U2001-FLT3)") (class "Default")
      (node (ref "C2007") (pin "2") (pinfunction "2_2") (pintype "passive"))
      (node (ref "U2001") (pin "1") (pinfunction "FLT3_1") (pintype "passive"))
    )
    (net (code "43") (name "Net-(U2001-FLT4)") (class "Default")
      (node (ref "C2003") (pin "1") (pinfunction "1_1") (pintype "passive"))
      (node (ref "U2001") (pin "14") (pinfunction "FLT4_14") (pintype "passive"))
    )
    (net (code "44") (name "Net-(U2001-RFIN)") (class "Default")
      (node (ref "C2008") (pin "2") (pinfunction "2_2") (pintype "passive"))
      (node (ref "U2001") (pin "2") (pinfunction "RFIN_2") (pintype "passive"))
    )
    (net (code "45") (name "Net-(U2002A-+)") (class "Default")
      (node (ref "C2009") (pin "2") (pinfunction "2_2") (pintype "passive"))
      (node (ref "R2003") (pin "2") (pinfunction "2_2") (pintype "passive"))
      (node (ref "U2002") (pin "3") (pinfunction "+_3") (pintype "passive"))
    )
    (net (code "46") (name "Net-(U2002A--)") (class "Default")
      (node (ref "R2018") (pin "2") (pinfunction "2_2") (pintype "passive"))
      (node (ref "R2019") (pin "1") (pinfunction "1_1") (pintype "passive"))
      (node (ref "U2002") (pin "2") (pinfunction "-_2") (pintype "passive"))
    )
    (net (code "47") (name "Net-(U2002B-+)") (class "Default")
      (node (ref "R2002") (pin "1") (pinfunction "1_1") (pintype "passive"))
      (node (ref "R2006") (pin "2") (pinfunction "2_2") (pintype "passive"))
      (node (ref "U2002") (pin "5") (pinfunction "+_5") (pintype "passive"))
    )
    (net (code "48") (name "Net-(U2002B--)") (class "Default")
      (node (ref "R2013") (pin "2") (pinfunction "2_2") (pintype "passive"))
      (node (ref "R2017") (pin "1") (pinfunction "1_1") (pintype "passive"))
      (node (ref "U2002") (pin "6") (pinfunction "-_6") (pintype "passive"))
    )
    (net (code "49") (name "Net-(U2003-ENBL)") (class "Default")
      (node (ref "R2035") (pin "2") (pinfunction "2_2") (pintype "passive"))
      (node (ref "U2003") (pin "4") (pinfunction "ENBL_4") (pintype "passive"))
    )
    (net (code "50") (name "Net-(U2003-FLT1)") (class "Default")
      (node (ref "C2026") (pin "2") (pinfunction "2_2") (pintype "passive"))
      (node (ref "U2003") (pin "3") (pinfunction "FLT1_3") (pintype "passive"))
    )
    (net (code "51") (name "Net-(U2003-FLT2)") (class "Default")
      (node (ref "C2018") (pin "1") (pinfunction "1_1") (pintype "passive"))
      (node (ref "U2003") (pin "16") (pinfunction "FLT2_16") (pintype "passive"))
    )
    (net (code "52") (name "Net-(U2003-FLT3)") (class "Default")
      (node (ref "C2021") (pin "2") (pinfunction "2_2") (pintype "passive"))
      (node (ref "U2003") (pin "1") (pinfunction "FLT3_1") (pintype "passive"))
    )
    (net (code "53") (name "Net-(U2003-FLT4)") (class "Default")
      (node (ref "C2017") (pin "1") (pinfunction "1_1") (pintype "passive"))
      (node (ref "U2003") (pin "14") (pinfunction "FLT4_14") (pintype "passive"))
    )
    (net (code "54") (name "Net-(U2003-RFIN)") (class "Default")
      (node (ref "C2022") (pin "2") (pinfunction "2_2") (pintype "passive"))
      (node (ref "U2003") (pin "2") (pinfunction "RFIN_2") (pintype "passive"))
    )
    (net (code "55") (name "Net-(U2004A-+)") (class "Default")
      (node (ref "C2025") (pin "2") (pinfunction "2_2") (pintype "passive"))
      (node (ref "R2026") (pin "2") (pinfunction "2_2") (pintype "passive"))
      (node (ref "U2004") (pin "3") (pinfunction "+_3") (pintype "passive"))
    )
    (net (code "56") (name "Net-(U2004A--)") (class "Default")
      (node (ref "R2037") (pin "2") (pinfunction "2_2") (pintype "passive"))
      (node (ref "R2038") (pin "1") (pinfunction "1_1") (pintype "passive"))
      (node (ref "U2004") (pin "2") (pinfunction "-_2") (pintype "passive"))
    )
    (net (code "57") (name "Net-(U2004B-+)") (class "Default")
      (node (ref "R2021") (pin "2") (pinfunction "2_2") (pintype "passive"))
      (node (ref "R2023") (pin "2") (pinfunction "2_2") (pintype "passive"))
      (node (ref "U2004") (pin "5") (pinfunction "+_5") (pintype "passive"))
    )
    (net (code "58") (name "Net-(U2004B--)") (class "Default")
      (node (ref "R2029") (pin "2") (pinfunction "2_2") (pintype "passive"))
      (node (ref "R2036") (pin "1") (pinfunction "1_1") (pintype "passive"))
      (node (ref "U2004") (pin "6") (pinfunction "-_6") (pintype "passive"))
    )
    (net (code "59") (name "Net-(U2005-ENBL)") (class "Default")
      (node (ref "R2054") (pin "2") (pinfunction "2_2") (pintype "passive"))
      (node (ref "U2005") (pin "4") (pinfunction "ENBL_4") (pintype "passive"))
    )
    (net (code "60") (name "Net-(U2005-FLT1)") (class "Default")
      (node (ref "C2040") (pin "2") (pinfunction "2_2") (pintype "passive"))
      (node (ref "U2005") (pin "3") (pinfunction "FLT1_3") (pintype "passive"))
    )
    (net (code "61") (name "Net-(U2005-FLT2)") (class "Default")
      (node (ref "C2032") (pin "1") (pinfunction "1_1") (pintype "passive"))
      (node (ref "U2005") (pin "16") (pinfunction "FLT2_16") (pintype "passive"))
    )
    (net (code "62") (name "Net-(U2005-FLT3)") (class "Default")
      (node (ref "C2035") (pin "2") (pinfunction "2_2") (pintype "passive"))
      (node (ref "U2005") (pin "1") (pinfunction "FLT3_1") (pintype "passive"))
    )
    (net (code "63") (name "Net-(U2005-FLT4)") (class "Default")
      (node (ref "C2031") (pin "1") (pinfunction "1_1") (pintype "passive"))
      (node (ref "U2005") (pin "14") (pinfunction "FLT4_14") (pintype "passive"))
    )
    (net (code "64") (name "Net-(U2005-RFIN)") (class "Default")
      (node (ref "C2036") (pin "2") (pinfunction "2_2") (pintype "passive"))
      (node (ref "U2005") (pin "2") (pinfunction "RFIN_2") (pintype "passive"))
    )
    (net (code "65") (name "Net-(U2006A-+)") (class "Default")
      (node (ref "C2039") (pin "2") (pinfunction "2_2") (pintype "passive"))
      (node (ref "R2045") (pin "2") (pinfunction "2_2") (pintype "passive"))
      (node (ref "U2006") (pin "3") (pinfunction "+_3") (pintype "passive"))
    )
    (net (code "66") (name "Net-(U2006A--)") (class "Default")
      (node (ref "R2056") (pin "2") (pinfunction "2_2") (pintype "passive"))
      (node (ref "R2057") (pin "1") (pinfunction "1_1") (pintype "passive"))
      (node (ref "U2006") (pin "2") (pinfunction "-_2") (pintype "passive"))
    )
    (net (code "67") (name "Net-(U2006B-+)") (class "Default")
      (node (ref "R2039") (pin "2") (pinfunction "2_2") (pintype "passive"))
      (node (ref "R2042") (pin "2") (pinfunction "2_2") (pintype "passive"))
      (node (ref "U2006") (pin "5") (pinfunction "+_5") (pintype "passive"))
    )
    (net (code "68") (name "Net-(U2006B--)") (class "Default")
      (node (ref "R2047") (pin "2") (pinfunction "2_2") (pintype "passive"))
      (node (ref "R2055") (pin "1") (pinfunction "1_1") (pintype "passive"))
      (node (ref "U2006") (pin "6") (pinfunction "-_6") (pintype "passive"))
    )
    (net (code "69") (name "unconnected-(U2001-NC-Pad6)") (class "Default")
      (node (ref "U2001") (pin "6") (pinfunction "NC_6") (pintype "passive+no_connect"))
    )
    (net (code "70") (name "unconnected-(U2001-NC-Pad7)") (class "Default")
      (node (ref "U2001") (pin "7") (pinfunction "NC_7") (pintype "passive+no_connect"))
    )
    (net (code "71") (name "unconnected-(U2001-NC-Pad8)") (class "Default")
      (node (ref "U2001") (pin "8") (pinfunction "NC_8") (pintype "passive+no_connect"))
    )
    (net (code "72") (name "unconnected-(U2001-NC-Pad12)") (class "Default")
      (node (ref "U2001") (pin "12") (pinfunction "NC_12") (pintype "passive+no_connect"))
    )
    (net (code "73") (name "unconnected-(U2001-NC-Pad13)") (class "Default")
      (node (ref "U2001") (pin "13") (pinfunction "NC_13") (pintype "passive+no_connect"))
    )
    (net (code "74") (name "unconnected-(U2003-NC-Pad6)") (class "Default")
      (node (ref "U2003") (pin "6") (pinfunction "NC_6") (pintype "passive+no_connect"))
    )
    (net (code "75") (name "unconnected-(U2003-NC-Pad7)") (class "Default")
      (node (ref "U2003") (pin "7") (pinfunction "NC_7") (pintype "passive+no_connect"))
    )
    (net (code "76") (name "unconnected-(U2003-NC-Pad8)") (class "Default")
      (node (ref "U2003") (pin "8") (pinfunction "NC_8") (pintype "passive+no_connect"))
    )
    (net (code "77") (name "unconnected-(U2003-NC-Pad12)") (class "Default")
      (node (ref "U2003") (pin "12") (pinfunction "NC_12") (pintype "passive"))
    )
    (net (code "78") (name "unconnected-(U2003-NC-Pad13)") (class "Default")
      (node (ref "U2003") (pin "13") (pinfunction "NC_13") (pintype "passive+no_connect"))
    )
    (net (code "79") (name "unconnected-(U2005-NC-Pad6)") (class "Default")
      (node (ref "U2005") (pin "6") (pinfunction "NC_6") (pintype "passive+no_connect"))
    )
    (net (code "80") (name "unconnected-(U2005-NC-Pad7)") (class "Default")
      (node (ref "U2005") (pin "7") (pinfunction "NC_7") (pintype "passive+no_connect"))
    )
    (net (code "81") (name "unconnected-(U2005-NC-Pad8)") (class "Default")
      (node (ref "U2005") (pin "8") (pinfunction "NC_8") (pintype "passive+no_connect"))
    )
    (net (code "82") (name "unconnected-(U2005-NC-Pad12)") (class "Default")
      (node (ref "U2005") (pin "12") (pinfunction "NC_12") (pintype "passive"))
    )
    (net (code "83") (name "unconnected-(U2005-NC-Pad13)") (class "Default")
      (node (ref "U2005") (pin "13") (pinfunction "NC_13") (pintype "passive+no_connect"))
    )
  )
)
